# 8_RK3588_EMMCIO_VCCIO2.net
KiCad netlist of a schematic drawn in Altium Designer
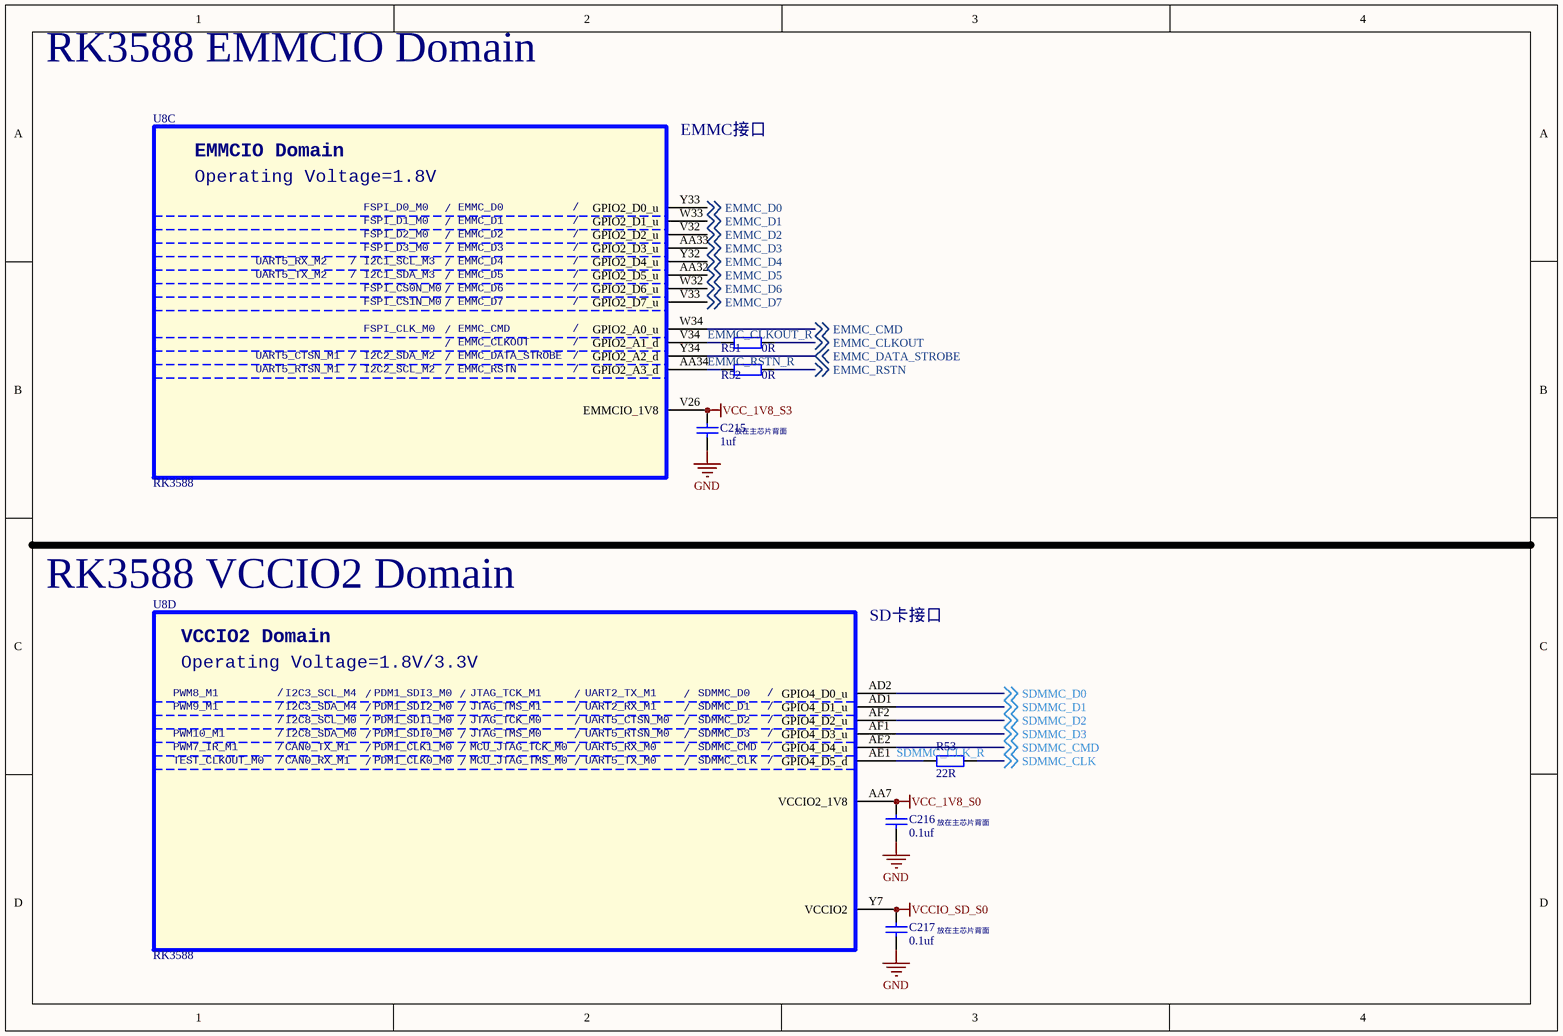
[diagram p0: 8.RK3588_EMMCIO_VCCIO2.SchDoc]

(export (version "E")
  (design (tool "Eeschema 10.0.6"))
  (components
    (comp (ref "C215")
      (value "1uf")
      (footprint "0.PCB1:C0201_L")
      (description "贴片电容/MLCC电容")
      (libsource (lib "RK3588") (part "C"))
    )
    (comp (ref "C216")
      (value "0.1uf")
      (footprint "0.PCB1:C0201_L")
      (description "贴片电容/MLCC电容")
      (libsource (lib "RK3588") (part "C"))
    )
    (comp (ref "C217")
      (value "0.1uf")
      (footprint "0.PCB1:C0201_L")
      (description "贴片电容/MLCC电容")
      (libsource (lib "RK3588") (part "C"))
    )
    (comp (ref "R51")
      (value "0R")
      (footprint "0.PCB1:R0201_L")
      (description "贴片电阻")
      (libsource (lib "RK3588") (part "R"))
    )
    (comp (ref "R52")
      (value "0R")
      (footprint "0.PCB1:R0201_L")
      (description "贴片电阻")
      (libsource (lib "RK3588") (part "R"))
    )
    (comp (ref "R53")
      (value "22R")
      (footprint "0.PCB1:R0402_L")
      (description "贴片电阻")
      (libsource (lib "RK3588") (part "R"))
    )
    (comp (ref "U8")
      (value "RK3588")
      (footprint "0.PCB1:BGA1088_23R00X23R00X2R00")
      (description "ROCKCHIP SOC")
      (libsource (lib "RK3588") (part "SOC_RK3588"))
    )
  )
  (nets
    (net (code "1") (name "/EMMC_CLKOUT_R") (class "Default")
      (node (ref "R51") (pin "1") (pinfunction "1_1") (pintype "passive"))
      (node (ref "U8") (pin "V34") (pinfunction "GPIO2_A1_d_V34") (pintype "passive"))
    )
    (net (code "2") (name "/EMMC_RSTN_R") (class "Default")
      (node (ref "R52") (pin "1") (pinfunction "1_1") (pintype "passive"))
      (node (ref "U8") (pin "AA34") (pinfunction "GPIO2_A3_d_AA34") (pintype "passive"))
    )
    (net (code "3") (name "/SDMMC_CLK_R") (class "Default")
      (node (ref "R53") (pin "1") (pinfunction "1_1") (pintype "passive"))
      (node (ref "U8") (pin "AE1") (pinfunction "GPIO4_D5_d_AE1") (pintype "passive"))
    )
    (net (code "4") (name "EMMC_CLKOUT") (class "Default")
      (node (ref "R51") (pin "2") (pinfunction "2_2") (pintype "passive"))
    )
    (net (code "5") (name "EMMC_CMD") (class "Default")
      (node (ref "U8") (pin "W34") (pinfunction "GPIO2_A0_u_W34") (pintype "passive"))
    )
    (net (code "6") (name "EMMC_D0") (class "Default")
      (node (ref "U8") (pin "Y33") (pinfunction "GPIO2_D0_u_Y33") (pintype "passive"))
    )
    (net (code "7") (name "EMMC_D1") (class "Default")
      (node (ref "U8") (pin "W33") (pinfunction "GPIO2_D1_u_W33") (pintype "passive"))
    )
    (net (code "8") (name "EMMC_D2") (class "Default")
      (node (ref "U8") (pin "V32") (pinfunction "GPIO2_D2_u_V32") (pintype "passive"))
    )
    (net (code "9") (name "EMMC_D3") (class "Default")
      (node (ref "U8") (pin "AA33") (pinfunction "GPIO2_D3_u_AA33") (pintype "passive"))
    )
    (net (code "10") (name "EMMC_D4") (class "Default")
      (node (ref "U8") (pin "Y32") (pinfunction "GPIO2_D4_u_Y32") (pintype "passive"))
    )
    (net (code "11") (name "EMMC_D5") (class "Default")
      (node (ref "U8") (pin "AA32") (pinfunction "GPIO2_D5_u_AA32") (pintype "passive"))
    )
    (net (code "12") (name "EMMC_D6") (class "Default")
      (node (ref "U8") (pin "W32") (pinfunction "GPIO2_D6_u_W32") (pintype "passive"))
    )
    (net (code "13") (name "EMMC_D7") (class "Default")
      (node (ref "U8") (pin "V33") (pinfunction "GPIO2_D7_u_V33") (pintype "passive"))
    )
    (net (code "14") (name "EMMC_DATA_STROBE") (class "Default")
      (node (ref "U8") (pin "Y34") (pinfunction "GPIO2_A2_d_Y34") (pintype "passive"))
    )
    (net (code "15") (name "EMMC_RSTN") (class "Default")
      (node (ref "R52") (pin "2") (pinfunction "2_2") (pintype "passive"))
    )
    (net (code "16") (name "GND") (class "Default")
      (node (ref "C215") (pin "1") (pinfunction "1_1") (pintype "passive"))
      (node (ref "C216") (pin "1") (pinfunction "1_1") (pintype "passive"))
      (node (ref "C217") (pin "1") (pinfunction "1_1") (pintype "passive"))
    )
    (net (code "17") (name "SDMMC_CLK") (class "Default")
      (node (ref "R53") (pin "2") (pinfunction "2_2") (pintype "passive"))
    )
    (net (code "18") (name "SDMMC_CMD") (class "Default")
      (node (ref "U8") (pin "AE2") (pinfunction "GPIO4_D4_u_AE2") (pintype "passive"))
    )
    (net (code "19") (name "SDMMC_D0") (class "Default")
      (node (ref "U8") (pin "AD2") (pinfunction "GPIO4_D0_u_AD2") (pintype "passive"))
    )
    (net (code "20") (name "SDMMC_D1") (class "Default")
      (node (ref "U8") (pin "AD1") (pinfunction "GPIO4_D1_u_AD1") (pintype "passive"))
    )
    (net (code "21") (name "SDMMC_D2") (class "Default")
      (node (ref "U8") (pin "AF2") (pinfunction "GPIO4_D2_u_AF2") (pintype "passive"))
    )
    (net (code "22") (name "SDMMC_D3") (class "Default")
      (node (ref "U8") (pin "AF1") (pinfunction "GPIO4_D3_u_AF1") (pintype "passive"))
    )
    (net (code "23") (name "VCCIO_SD_S0") (class "Default")
      (node (ref "C217") (pin "2") (pinfunction "2_2") (pintype "passive"))
      (node (ref "U8") (pin "Y7") (pinfunction "VCCIO2_Y7") (pintype "power_in"))
    )
    (net (code "24") (name "VCC_1V8_S0") (class "Default")
      (node (ref "C216") (pin "2") (pinfunction "2_2") (pintype "passive"))
      (node (ref "U8") (pin "AA7") (pinfunction "VCCIO2_1V8_AA7") (pintype "power_in"))
    )
    (net (code "25") (name "VCC_1V8_S3") (class "Default")
      (node (ref "C215") (pin "2") (pinfunction "2_2") (pintype "passive"))
      (node (ref "U8") (pin "V26") (pinfunction "EMMCIO_1V8_V26") (pintype "power_in"))
    )
  )
)
